# memory.net
KiCad netlist of a schematic drawn in Altium Designer
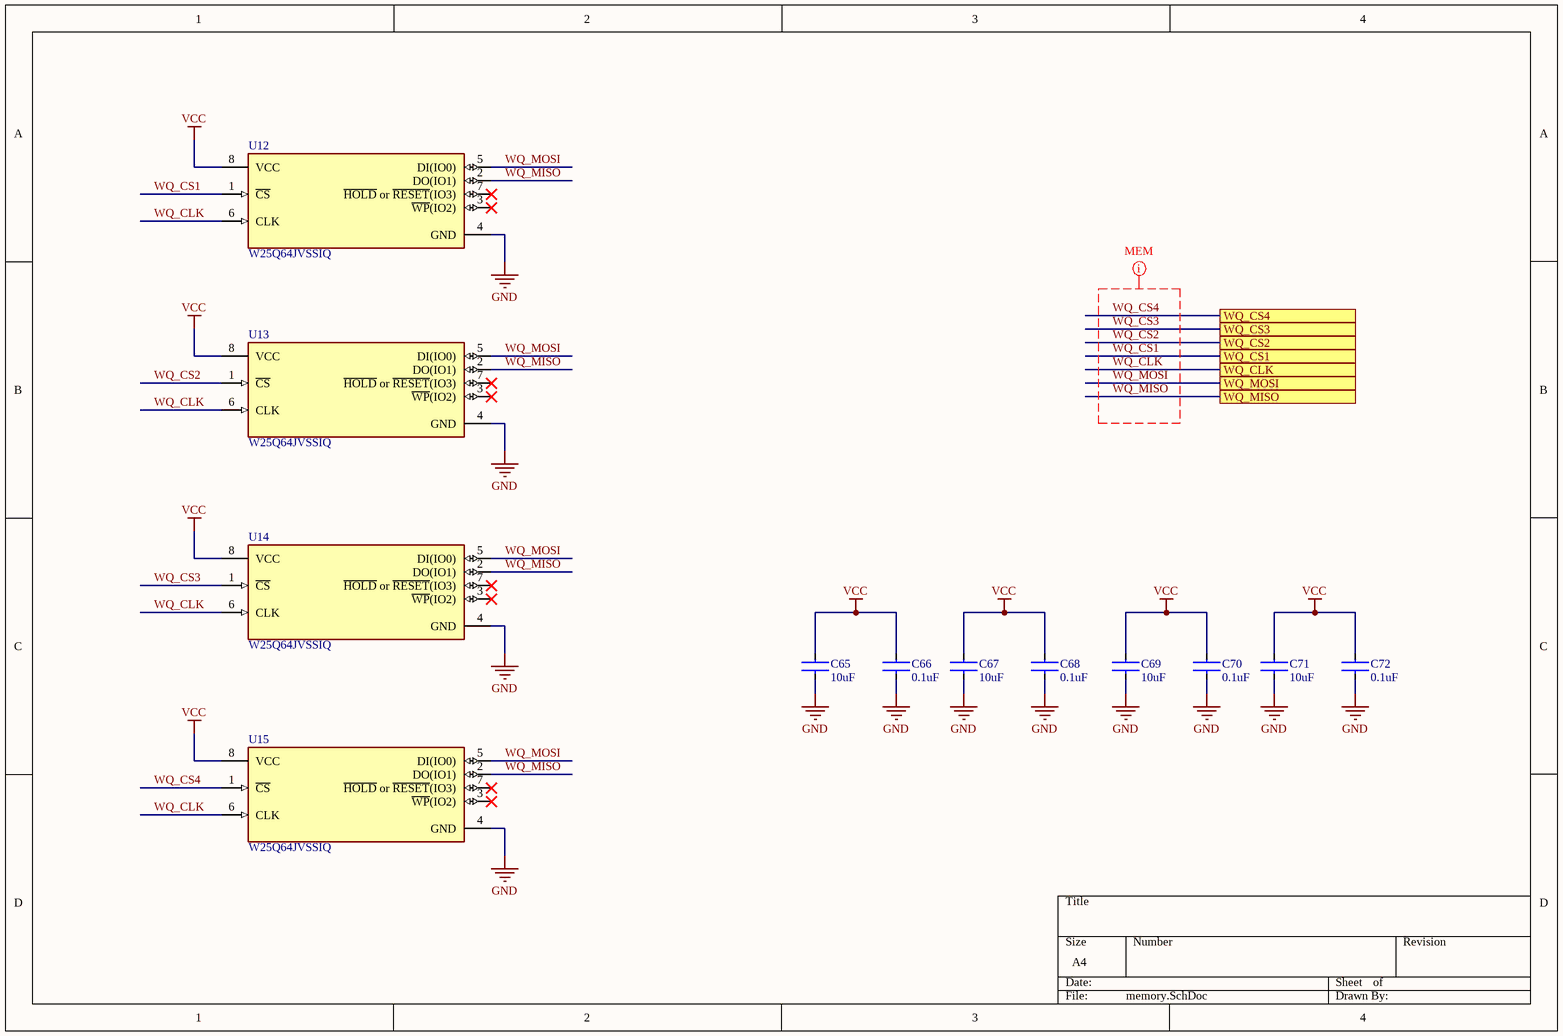
[diagram p0: memory.SchDoc]

(export (version "E")
  (design (tool "Eeschema 10.0.6"))
  (components
    (comp (ref "C65")
      (value "10uF")
      (footprint "C0402")
      (description "Cap Ceramic 10uF 16V X7R 10% Pad SMD 1206 125°C T/R")
      (fields
        (field (name "MANUFACTURER") "Samsung")
        (field (name "MANUFACTURER PART NUMBER") "CL31B106KOHNNNE")
      )
      (libsource (lib "afra") (part "CL31B106KOHNNNE"))
    )
    (comp (ref "C66")
      (value "0.1uF")
      (footprint "C0402")
      (description "Ceramic capacitor SMD-1206 100nF /50V X7R# K +-10%, Samsung, RoHS")
      (fields
        (field (name "MANUFACTURER") "Samsung")
        (field (name "MANUFACTURER PART NUMBER") "CL31B104KBCNNNC")
      )
      (libsource (lib "afra") (part "CL31B104KBCNNNC"))
    )
    (comp (ref "C67")
      (value "10uF")
      (footprint "C0402")
      (description "Cap Ceramic 10uF 16V X7R 10% Pad SMD 1206 125°C T/R")
      (fields
        (field (name "MANUFACTURER") "Samsung")
        (field (name "MANUFACTURER PART NUMBER") "CL31B106KOHNNNE")
      )
      (libsource (lib "afra") (part "CL31B106KOHNNNE"))
    )
    (comp (ref "C68")
      (value "0.1uF")
      (footprint "C0402")
      (description "Ceramic capacitor SMD-1206 100nF /50V X7R# K +-10%, Samsung, RoHS")
      (fields
        (field (name "MANUFACTURER") "Samsung")
        (field (name "MANUFACTURER PART NUMBER") "CL31B104KBCNNNC")
      )
      (libsource (lib "afra") (part "CL31B104KBCNNNC"))
    )
    (comp (ref "C69")
      (value "10uF")
      (footprint "C0402")
      (description "Cap Ceramic 10uF 16V X7R 10% Pad SMD 1206 125°C T/R")
      (fields
        (field (name "MANUFACTURER") "Samsung")
        (field (name "MANUFACTURER PART NUMBER") "CL31B106KOHNNNE")
      )
      (libsource (lib "afra") (part "CL31B106KOHNNNE"))
    )
    (comp (ref "C70")
      (value "0.1uF")
      (footprint "C0402")
      (description "Ceramic capacitor SMD-1206 100nF /50V X7R# K +-10%, Samsung, RoHS")
      (fields
        (field (name "MANUFACTURER") "Samsung")
        (field (name "MANUFACTURER PART NUMBER") "CL31B104KBCNNNC")
      )
      (libsource (lib "afra") (part "CL31B104KBCNNNC"))
    )
    (comp (ref "C71")
      (value "10uF")
      (footprint "C0402")
      (description "Cap Ceramic 10uF 16V X7R 10% Pad SMD 1206 125°C T/R")
      (fields
        (field (name "MANUFACTURER") "Samsung")
        (field (name "MANUFACTURER PART NUMBER") "CL31B106KOHNNNE")
      )
      (libsource (lib "afra") (part "CL31B106KOHNNNE"))
    )
    (comp (ref "C72")
      (value "0.1uF")
      (footprint "C0402")
      (description "Ceramic capacitor SMD-1206 100nF /50V X7R# K +-10%, Samsung, RoHS")
      (fields
        (field (name "MANUFACTURER") "Samsung")
        (field (name "MANUFACTURER PART NUMBER") "CL31B104KBCNNNC")
      )
      (libsource (lib "afra") (part "CL31B104KBCNNNC"))
    )
    (comp (ref "U12")
      (value "W25Q64JVSSIQ")
      (footprint "SOIC-8")
      (description "IC FLASH 64MBIT 104MHZ 8SOIC")
      (fields (field (name "MANUFACTURER") "Winbond"))
      (libsource (lib "afra") (part "W25Q64JVSSIQ"))
    )
    (comp (ref "U13")
      (value "W25Q64JVSSIQ")
      (footprint "SOIC-8")
      (description "IC FLASH 64MBIT 104MHZ 8SOIC")
      (fields (field (name "MANUFACTURER") "Winbond"))
      (libsource (lib "afra") (part "W25Q64JVSSIQ"))
    )
    (comp (ref "U14")
      (value "W25Q64JVSSIQ")
      (footprint "SOIC-8")
      (description "IC FLASH 64MBIT 104MHZ 8SOIC")
      (fields (field (name "MANUFACTURER") "Winbond"))
      (libsource (lib "afra") (part "W25Q64JVSSIQ"))
    )
    (comp (ref "U15")
      (value "W25Q64JVSSIQ")
      (footprint "SOIC-8")
      (description "IC FLASH 64MBIT 104MHZ 8SOIC")
      (fields (field (name "MANUFACTURER") "Winbond"))
      (libsource (lib "afra") (part "W25Q64JVSSIQ"))
    )
  )
  (nets
    (net (code "1") (name "/WQ_CLK") (class "Default")
      (node (ref "U12") (pin "6") (pinfunction "CLK_6") (pintype "input"))
      (node (ref "U13") (pin "6") (pinfunction "CLK_6") (pintype "input"))
      (node (ref "U14") (pin "6") (pinfunction "CLK_6") (pintype "input"))
      (node (ref "U15") (pin "6") (pinfunction "CLK_6") (pintype "input"))
    )
    (net (code "2") (name "/WQ_CS1") (class "Default")
      (node (ref "U12") (pin "1") (pinfunction "~{CS}_1") (pintype "input"))
    )
    (net (code "3") (name "/WQ_CS2") (class "Default")
      (node (ref "U13") (pin "1") (pinfunction "~{CS}_1") (pintype "input"))
    )
    (net (code "4") (name "/WQ_CS3") (class "Default")
      (node (ref "U14") (pin "1") (pinfunction "~{CS}_1") (pintype "input"))
    )
    (net (code "5") (name "/WQ_CS4") (class "Default")
      (node (ref "U15") (pin "1") (pinfunction "~{CS}_1") (pintype "input"))
    )
    (net (code "6") (name "/WQ_MISO") (class "Default")
      (node (ref "U12") (pin "2") (pinfunction "DO(IO1)_2") (pintype "bidirectional"))
      (node (ref "U13") (pin "2") (pinfunction "DO(IO1)_2") (pintype "bidirectional"))
      (node (ref "U14") (pin "2") (pinfunction "DO(IO1)_2") (pintype "bidirectional"))
      (node (ref "U15") (pin "2") (pinfunction "DO(IO1)_2") (pintype "bidirectional"))
    )
    (net (code "7") (name "/WQ_MOSI") (class "Default")
      (node (ref "U12") (pin "5") (pinfunction "DI(IO0)_5") (pintype "bidirectional"))
      (node (ref "U13") (pin "5") (pinfunction "DI(IO0)_5") (pintype "bidirectional"))
      (node (ref "U14") (pin "5") (pinfunction "DI(IO0)_5") (pintype "bidirectional"))
      (node (ref "U15") (pin "5") (pinfunction "DI(IO0)_5") (pintype "bidirectional"))
    )
    (net (code "8") (name "GND") (class "Default")
      (node (ref "C65") (pin "2") (pinfunction "2_2") (pintype "passive"))
      (node (ref "C66") (pin "2") (pinfunction "2_2") (pintype "passive"))
      (node (ref "C67") (pin "2") (pinfunction "2_2") (pintype "passive"))
      (node (ref "C68") (pin "2") (pinfunction "2_2") (pintype "passive"))
      (node (ref "C69") (pin "2") (pinfunction "2_2") (pintype "passive"))
      (node (ref "C70") (pin "2") (pinfunction "2_2") (pintype "passive"))
      (node (ref "C71") (pin "2") (pinfunction "2_2") (pintype "passive"))
      (node (ref "C72") (pin "2") (pinfunction "2_2") (pintype "passive"))
      (node (ref "U12") (pin "4") (pinfunction "GND_4") (pintype "power_in"))
      (node (ref "U13") (pin "4") (pinfunction "GND_4") (pintype "power_in"))
      (node (ref "U14") (pin "4") (pinfunction "GND_4") (pintype "power_in"))
      (node (ref "U15") (pin "4") (pinfunction "GND_4") (pintype "power_in"))
    )
    (net (code "9") (name "VCC") (class "Default")
      (node (ref "C65") (pin "1") (pinfunction "1_1") (pintype "passive"))
      (node (ref "C66") (pin "1") (pinfunction "1_1") (pintype "passive"))
      (node (ref "C67") (pin "1") (pinfunction "1_1") (pintype "passive"))
      (node (ref "C68") (pin "1") (pinfunction "1_1") (pintype "passive"))
      (node (ref "C69") (pin "1") (pinfunction "1_1") (pintype "passive"))
      (node (ref "C70") (pin "1") (pinfunction "1_1") (pintype "passive"))
      (node (ref "C71") (pin "1") (pinfunction "1_1") (pintype "passive"))
      (node (ref "C72") (pin "1") (pinfunction "1_1") (pintype "passive"))
      (node (ref "U12") (pin "8") (pinfunction "VCC_8") (pintype "power_in"))
      (node (ref "U13") (pin "8") (pinfunction "VCC_8") (pintype "power_in"))
      (node (ref "U14") (pin "8") (pinfunction "VCC_8") (pintype "power_in"))
      (node (ref "U15") (pin "8") (pinfunction "VCC_8") (pintype "power_in"))
    )
    (net (code "10") (name "unconnected-(U12-~{HOLD}_or_~{RESET}(IO3)-Pad7)") (class "Default")
      (node (ref "U12") (pin "7") (pinfunction "~{HOLD}_or_~{RESET}(IO3)_7") (pintype "bidirectional+no_connect"))
    )
    (net (code "11") (name "unconnected-(U12-~{WP}(IO2)-Pad3)") (class "Default")
      (node (ref "U12") (pin "3") (pinfunction "~{WP}(IO2)_3") (pintype "bidirectional+no_connect"))
    )
    (net (code "12") (name "unconnected-(U13-~{HOLD}_or_~{RESET}(IO3)-Pad7)") (class "Default")
      (node (ref "U13") (pin "7") (pinfunction "~{HOLD}_or_~{RESET}(IO3)_7") (pintype "bidirectional+no_connect"))
    )
    (net (code "13") (name "unconnected-(U13-~{WP}(IO2)-Pad3)") (class "Default")
      (node (ref "U13") (pin "3") (pinfunction "~{WP}(IO2)_3") (pintype "bidirectional+no_connect"))
    )
    (net (code "14") (name "unconnected-(U14-~{HOLD}_or_~{RESET}(IO3)-Pad7)") (class "Default")
      (node (ref "U14") (pin "7") (pinfunction "~{HOLD}_or_~{RESET}(IO3)_7") (pintype "bidirectional+no_connect"))
    )
    (net (code "15") (name "unconnected-(U14-~{WP}(IO2)-Pad3)") (class "Default")
      (node (ref "U14") (pin "3") (pinfunction "~{WP}(IO2)_3") (pintype "bidirectional+no_connect"))
    )
    (net (code "16") (name "unconnected-(U15-~{HOLD}_or_~{RESET}(IO3)-Pad7)") (class "Default")
      (node (ref "U15") (pin "7") (pinfunction "~{HOLD}_or_~{RESET}(IO3)_7") (pintype "bidirectional+no_connect"))
    )
    (net (code "17") (name "unconnected-(U15-~{WP}(IO2)-Pad3)") (class "Default")
      (node (ref "U15") (pin "3") (pinfunction "~{WP}(IO2)_3") (pintype "bidirectional+no_connect"))
    )
  )
)
